# dali.net
KiCad netlist of a schematic drawn in EAGLE
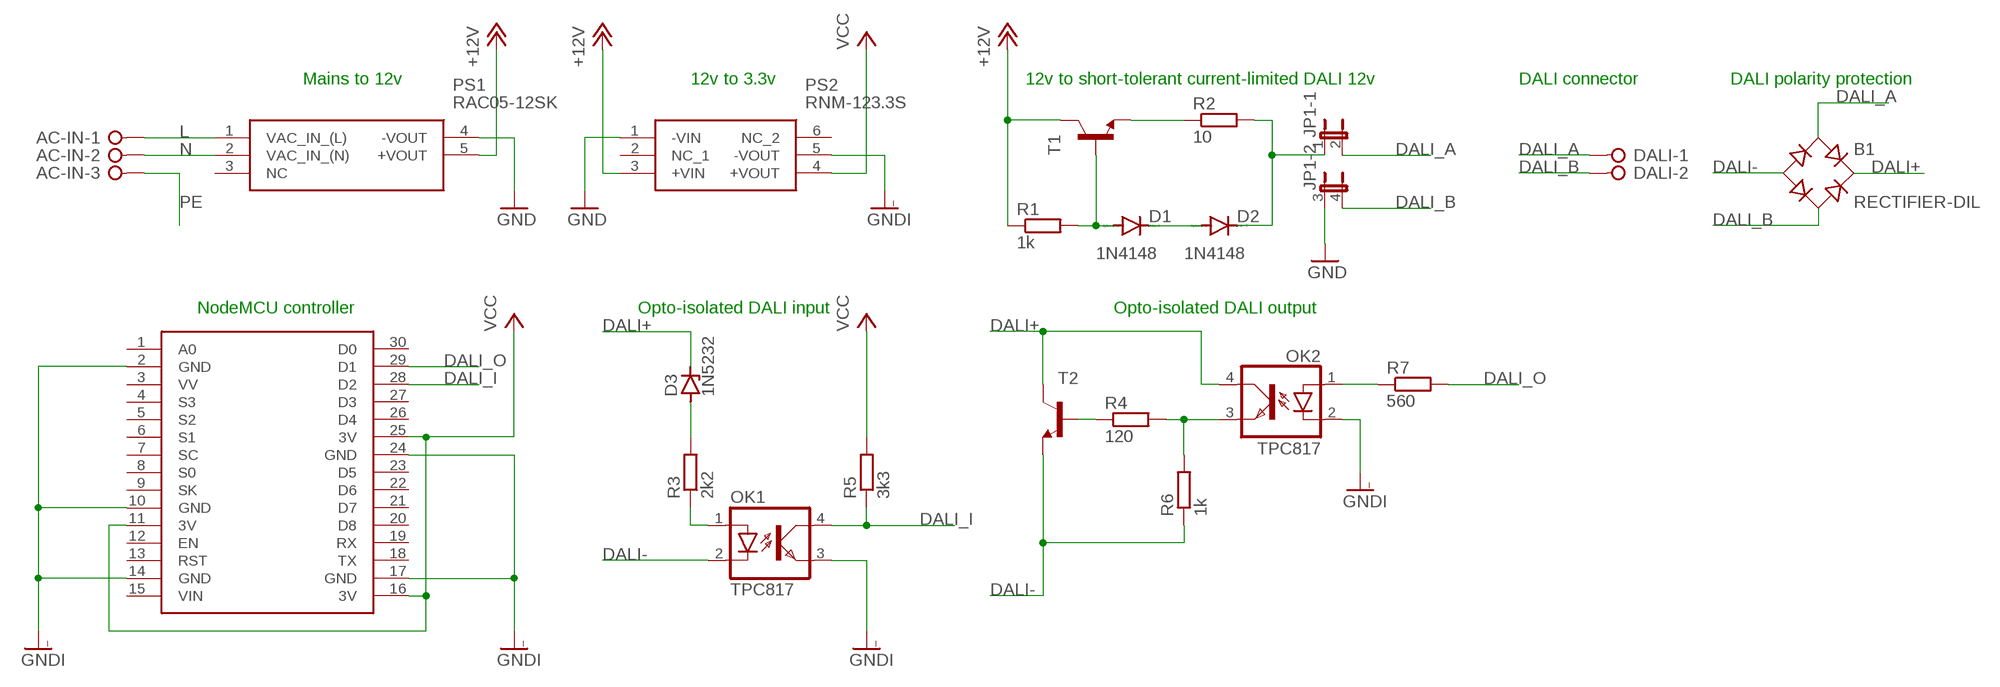
[diagram p0: schematic, sheet 1]

(export (version "E")
  (design (tool "Eeschema 10.0.6"))
  (components
    (comp (ref "AC-IN")
      (value "39544-3003")
      (footprint "eagle-import:39544-3003")
      (libsource (lib "eagle-import") (part "39544-3003"))
    )
    (comp (ref "B1")
      (value "RECTIFIER-DIL")
      (footprint "eagle-import:B-DIL")
      (libsource (lib "eagle-import") (part "RECTIFIER-DIL"))
    )
    (comp (ref "D1")
      (value "1N4148")
      (footprint "eagle-import:DO35-10")
      (libsource (lib "eagle-import") (part "1N4148DO35-10"))
    )
    (comp (ref "D2")
      (value "1N4148")
      (footprint "eagle-import:DO35-10")
      (libsource (lib "eagle-import") (part "1N4148DO35-10"))
    )
    (comp (ref "D3")
      (value "1N5232")
      (footprint "eagle-import:DO35Z10")
      (libsource (lib "eagle-import") (part "ZENER-DIODEDO35Z10"))
    )
    (comp (ref "DALI")
      (value "39544-3002")
      (footprint "eagle-import:39544-3002")
      (libsource (lib "eagle-import") (part "39544-3002"))
    )
    (comp (ref "JP1")
      (value "JP2QE")
      (footprint "eagle-import:JP2Q")
      (libsource (lib "eagle-import") (part "JP2QE"))
    )
    (comp (ref "OK1")
      (value "TPC817")
      (footprint "eagle-import:DIL04")
      (fields (field (name "SPICEPREFIX") "O"))
      (libsource (lib "eagle-import") (part "TIL191"))
    )
    (comp (ref "OK2")
      (value "TPC817")
      (footprint "eagle-import:DIL04")
      (libsource (lib "eagle-import") (part "TIL191"))
    )
    (comp (ref "PS1")
      (value "RAC05-12SK")
      (footprint "eagle-import:RAC05-12SK")
      (fields (field (name "MOUSER_PART_NUMBER") "919-RAC05-12SK"))
      (libsource (lib "eagle-import") (part "RAC05-12SK"))
    )
    (comp (ref "PS2")
      (value "RNM-123.3S")
      (footprint "eagle-import:DIP508W115P254L830H705Q6N")
      (libsource (lib "eagle-import") (part "RNM-123.3S"))
    )
    (comp (ref "R1")
      (value "1k")
      (footprint "eagle-import:0207_7")
      (libsource (lib "eagle-import") (part "R-EU_0207/7"))
    )
    (comp (ref "R2")
      (value "10")
      (footprint "eagle-import:0207_7")
      (libsource (lib "eagle-import") (part "R-EU_0207/7"))
    )
    (comp (ref "R3")
      (value "2k2")
      (footprint "eagle-import:0207_7")
      (libsource (lib "eagle-import") (part "R-EU_0207/7"))
    )
    (comp (ref "R4")
      (value "120")
      (footprint "eagle-import:0207_7")
      (libsource (lib "eagle-import") (part "R-EU_0207/7"))
    )
    (comp (ref "R5")
      (value "3k3")
      (footprint "eagle-import:0207_7")
      (libsource (lib "eagle-import") (part "R-EU_0207/7"))
    )
    (comp (ref "R6")
      (value "1k")
      (footprint "eagle-import:0207_7")
      (libsource (lib "eagle-import") (part "R-EU_0207/7"))
    )
    (comp (ref "R7")
      (value "560")
      (footprint "eagle-import:0207_7")
      (libsource (lib "eagle-import") (part "R-EU_0207/7"))
    )
    (comp (ref "T1")
      (value "MPS2222A-NPN-TO92-CBE")
      (footprint "eagle-import:TO92-CBE")
      (libsource (lib "eagle-import") (part "-NPN-TO92-CBEMPS2222A"))
    )
    (comp (ref "T2")
      (value "MPS2222A-NPN-TO92-CBE")
      (footprint "eagle-import:TO92-CBE")
      (libsource (lib "eagle-import") (part "-NPN-TO92-CBEMPS2222A"))
    )
    (comp (ref "U$1")
      (value "NODEMCU")
      (footprint "eagle-import:NODEMCU")
      (libsource (lib "eagle-import") (part "NODEMCU"))
    )
  )
  (nets
    (net (code "1") (name "+12V") (class "Default")
      (node (ref "PS1") (pin "5") (pinfunction "+VOUT_5") (pintype "bidirectional"))
      (node (ref "PS2") (pin "3") (pinfunction "+VIN_3") (pintype "power_in"))
      (node (ref "R1") (pin "1") (pinfunction "1_1") (pintype "passive"))
      (node (ref "T1") (pin "C") (pinfunction "C_C") (pintype "passive"))
    )
    (net (code "2") (name "/DALI+") (class "Default")
      (node (ref "B1") (pin "+") (pinfunction "+_+") (pintype "passive"))
      (node (ref "D3") (pin "C") (pinfunction "C_C") (pintype "passive"))
      (node (ref "OK2") (pin "4") (pinfunction "COL_4") (pintype "passive"))
      (node (ref "T2") (pin "C") (pinfunction "C_C") (pintype "passive"))
    )
    (net (code "3") (name "/DALI-") (class "Default")
      (node (ref "B1") (pin "-") (pinfunction "-_-") (pintype "passive"))
      (node (ref "OK1") (pin "2") (pinfunction "C_2") (pintype "passive"))
      (node (ref "R6") (pin "1") (pinfunction "1_1") (pintype "passive"))
      (node (ref "T2") (pin "E") (pinfunction "E_E") (pintype "passive"))
    )
    (net (code "4") (name "/DALI_A") (class "Default")
      (node (ref "B1") (pin "AC1") (pinfunction "AC1_AC1") (pintype "passive"))
      (node (ref "DALI") (pin "1") (pinfunction "KL_1") (pintype "passive"))
      (node (ref "JP1") (pin "2") (pinfunction "2_2") (pintype "passive"))
    )
    (net (code "5") (name "/DALI_B") (class "Default")
      (node (ref "B1") (pin "AC2") (pinfunction "AC2_AC2") (pintype "passive"))
      (node (ref "DALI") (pin "2") (pinfunction "KL_2") (pintype "passive"))
      (node (ref "JP1") (pin "4") (pinfunction "2_4") (pintype "passive"))
    )
    (net (code "6") (name "/DALI_I") (class "Default")
      (node (ref "OK1") (pin "4") (pinfunction "COL_4") (pintype "passive"))
      (node (ref "R5") (pin "1") (pinfunction "1_1") (pintype "passive"))
      (node (ref "U$1") (pin "28") (pinfunction "D2_28") (pintype "bidirectional"))
    )
    (net (code "7") (name "/DALI_O") (class "Default")
      (node (ref "R7") (pin "2") (pinfunction "2_2") (pintype "passive"))
      (node (ref "U$1") (pin "29") (pinfunction "D1_29") (pintype "bidirectional"))
    )
    (net (code "8") (name "/L") (class "Default")
      (node (ref "AC-IN") (pin "1") (pinfunction "KL_1") (pintype "passive"))
      (node (ref "PS1") (pin "1") (pinfunction "VAC_IN_(L)_1") (pintype "bidirectional"))
    )
    (net (code "9") (name "/N") (class "Default")
      (node (ref "AC-IN") (pin "2") (pinfunction "KL_2") (pintype "passive"))
      (node (ref "PS1") (pin "2") (pinfunction "VAC_IN_(N)_2") (pintype "bidirectional"))
    )
    (net (code "10") (name "/PE") (class "Default")
      (node (ref "AC-IN") (pin "3") (pinfunction "KL_3") (pintype "passive"))
    )
    (net (code "11") (name "GND") (class "Default")
      (node (ref "JP1") (pin "3") (pinfunction "1_3") (pintype "passive"))
      (node (ref "PS1") (pin "4") (pinfunction "-VOUT_4") (pintype "bidirectional"))
      (node (ref "PS2") (pin "1") (pinfunction "-VIN_1") (pintype "power_in"))
    )
    (net (code "12") (name "GNDI") (class "Default")
      (node (ref "OK1") (pin "3") (pinfunction "EMIT_3") (pintype "passive"))
      (node (ref "OK2") (pin "2") (pinfunction "C_2") (pintype "passive"))
      (node (ref "PS2") (pin "5") (pinfunction "-VOUT_5") (pintype "output"))
      (node (ref "U$1") (pin "10") (pinfunction "GND_10") (pintype "power_in"))
      (node (ref "U$1") (pin "14") (pinfunction "GND_14") (pintype "power_in"))
      (node (ref "U$1") (pin "17") (pinfunction "GND_17") (pintype "power_in"))
      (node (ref "U$1") (pin "2") (pinfunction "GND_2") (pintype "power_in"))
      (node (ref "U$1") (pin "24") (pinfunction "GND_24") (pintype "power_in"))
    )
    (net (code "13") (name "Net-(D1-PadA)") (class "Default")
      (node (ref "D1") (pin "A") (pinfunction "A_A") (pintype "passive"))
      (node (ref "R1") (pin "2") (pinfunction "2_2") (pintype "passive"))
      (node (ref "T1") (pin "B") (pinfunction "B_B") (pintype "passive"))
    )
    (net (code "14") (name "Net-(D1-PadC)") (class "Default")
      (node (ref "D1") (pin "C") (pinfunction "C_C") (pintype "passive"))
      (node (ref "D2") (pin "A") (pinfunction "A_A") (pintype "passive"))
    )
    (net (code "15") (name "Net-(D2-PadC)") (class "Default")
      (node (ref "D2") (pin "C") (pinfunction "C_C") (pintype "passive"))
      (node (ref "JP1") (pin "1") (pinfunction "1_1") (pintype "passive"))
      (node (ref "R2") (pin "2") (pinfunction "2_2") (pintype "passive"))
    )
    (net (code "16") (name "Net-(D3-PadA)") (class "Default")
      (node (ref "D3") (pin "A") (pinfunction "A_A") (pintype "passive"))
      (node (ref "R3") (pin "2") (pinfunction "2_2") (pintype "passive"))
    )
    (net (code "17") (name "Net-(OK1-A)") (class "Default")
      (node (ref "OK1") (pin "1") (pinfunction "A_1") (pintype "passive"))
      (node (ref "R3") (pin "1") (pinfunction "1_1") (pintype "passive"))
    )
    (net (code "18") (name "Net-(OK2-A)") (class "Default")
      (node (ref "OK2") (pin "1") (pinfunction "A_1") (pintype "passive"))
      (node (ref "R7") (pin "1") (pinfunction "1_1") (pintype "passive"))
    )
    (net (code "19") (name "Net-(OK2-EMIT)") (class "Default")
      (node (ref "OK2") (pin "3") (pinfunction "EMIT_3") (pintype "passive"))
      (node (ref "R4") (pin "2") (pinfunction "2_2") (pintype "passive"))
      (node (ref "R6") (pin "2") (pinfunction "2_2") (pintype "passive"))
    )
    (net (code "20") (name "Net-(R2-Pad1)") (class "Default")
      (node (ref "R2") (pin "1") (pinfunction "1_1") (pintype "passive"))
      (node (ref "T1") (pin "E") (pinfunction "E_E") (pintype "passive"))
    )
    (net (code "21") (name "Net-(R4-Pad1)") (class "Default")
      (node (ref "R4") (pin "1") (pinfunction "1_1") (pintype "passive"))
      (node (ref "T2") (pin "B") (pinfunction "B_B") (pintype "passive"))
    )
    (net (code "22") (name "VCC") (class "Default")
      (node (ref "PS2") (pin "4") (pinfunction "+VOUT_4") (pintype "output"))
      (node (ref "R5") (pin "2") (pinfunction "2_2") (pintype "passive"))
      (node (ref "U$1") (pin "11") (pinfunction "3V_11") (pintype "power_in"))
      (node (ref "U$1") (pin "16") (pinfunction "3V_16") (pintype "power_in"))
      (node (ref "U$1") (pin "25") (pinfunction "3V_25") (pintype "power_in"))
    )
    (net (code "23") (name "unconnected-(PS1-NC-Pad3)") (class "Default")
      (node (ref "PS1") (pin "3") (pinfunction "NC_3") (pintype "no_connect"))
    )
    (net (code "24") (name "unconnected-(PS2-NC_1-Pad2)") (class "Default")
      (node (ref "PS2") (pin "2") (pinfunction "NC_1_2") (pintype "bidirectional"))
    )
    (net (code "25") (name "unconnected-(PS2-NC_2-Pad6)") (class "Default")
      (node (ref "PS2") (pin "6") (pinfunction "NC_2_6") (pintype "bidirectional"))
    )
    (net (code "26") (name "unconnected-(U$1-A0-Pad1)") (class "Default")
      (node (ref "U$1") (pin "1") (pinfunction "A0_1") (pintype "bidirectional"))
    )
    (net (code "27") (name "unconnected-(U$1-D0-Pad30)") (class "Default")
      (node (ref "U$1") (pin "30") (pinfunction "D0_30") (pintype "bidirectional"))
    )
    (net (code "28") (name "unconnected-(U$1-D3-Pad27)") (class "Default")
      (node (ref "U$1") (pin "27") (pinfunction "D3_27") (pintype "bidirectional"))
    )
    (net (code "29") (name "unconnected-(U$1-D4-Pad26)") (class "Default")
      (node (ref "U$1") (pin "26") (pinfunction "D4_26") (pintype "bidirectional"))
    )
    (net (code "30") (name "unconnected-(U$1-D5-Pad23)") (class "Default")
      (node (ref "U$1") (pin "23") (pinfunction "D5_23") (pintype "bidirectional"))
    )
    (net (code "31") (name "unconnected-(U$1-D6-Pad22)") (class "Default")
      (node (ref "U$1") (pin "22") (pinfunction "D6_22") (pintype "bidirectional"))
    )
    (net (code "32") (name "unconnected-(U$1-D7-Pad21)") (class "Default")
      (node (ref "U$1") (pin "21") (pinfunction "D7_21") (pintype "bidirectional"))
    )
    (net (code "33") (name "unconnected-(U$1-D8-Pad20)") (class "Default")
      (node (ref "U$1") (pin "20") (pinfunction "D8_20") (pintype "bidirectional"))
    )
    (net (code "34") (name "unconnected-(U$1-EN-Pad12)") (class "Default")
      (node (ref "U$1") (pin "12") (pinfunction "EN_12") (pintype "bidirectional"))
    )
    (net (code "35") (name "unconnected-(U$1-RST-Pad13)") (class "Default")
      (node (ref "U$1") (pin "13") (pinfunction "RST_13") (pintype "bidirectional"))
    )
    (net (code "36") (name "unconnected-(U$1-RX-Pad19)") (class "Default")
      (node (ref "U$1") (pin "19") (pinfunction "RX_19") (pintype "bidirectional"))
    )
    (net (code "37") (name "unconnected-(U$1-S0-Pad8)") (class "Default")
      (node (ref "U$1") (pin "8") (pinfunction "S0_8") (pintype "bidirectional"))
    )
    (net (code "38") (name "unconnected-(U$1-S1-Pad6)") (class "Default")
      (node (ref "U$1") (pin "6") (pinfunction "S1_6") (pintype "bidirectional"))
    )
    (net (code "39") (name "unconnected-(U$1-S2-Pad5)") (class "Default")
      (node (ref "U$1") (pin "5") (pinfunction "S2_5") (pintype "bidirectional"))
    )
    (net (code "40") (name "unconnected-(U$1-S3-Pad4)") (class "Default")
      (node (ref "U$1") (pin "4") (pinfunction "S3_4") (pintype "bidirectional"))
    )
    (net (code "41") (name "unconnected-(U$1-SC-Pad7)") (class "Default")
      (node (ref "U$1") (pin "7") (pinfunction "SC_7") (pintype "bidirectional"))
    )
    (net (code "42") (name "unconnected-(U$1-SK-Pad9)") (class "Default")
      (node (ref "U$1") (pin "9") (pinfunction "SK_9") (pintype "bidirectional"))
    )
    (net (code "43") (name "unconnected-(U$1-TX-Pad18)") (class "Default")
      (node (ref "U$1") (pin "18") (pinfunction "TX_18") (pintype "bidirectional"))
    )
    (net (code "44") (name "unconnected-(U$1-VIN-Pad15)") (class "Default")
      (node (ref "U$1") (pin "15") (pinfunction "VIN_15") (pintype "bidirectional"))
    )
    (net (code "45") (name "unconnected-(U$1-VV-Pad3)") (class "Default")
      (node (ref "U$1") (pin "3") (pinfunction "VV_3") (pintype "bidirectional"))
    )
  )
)
